# Tutorial.net
KiCad netlist of a schematic drawn in Altium Designer
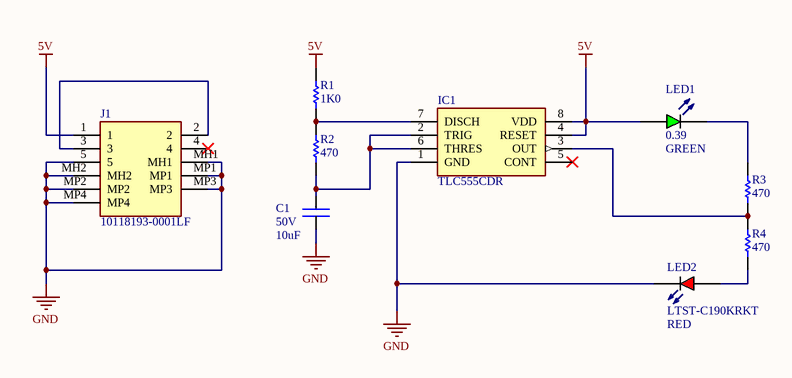
[diagram p0: Tutorial.SchDoc]

(export (version "E")
  (design (tool "Eeschema 10.0.6"))
  (components
    (comp (ref "C1")
      (value "10uF")
      (footprint "AquaDrone:CAPC3225X28N")
      (description "CAP CER 10UF 50V X7S 1210")
      (fields
        (field (name "MFG") "Taiyo Yuden")
        (field (name "MFG_PART_NO") "UMK325C7106MM-T")
        (field (name "VOLTAGE") "50V")
      )
      (libsource (lib "AquaDrone") (part "CAP CER 10UF 50V X7S 1210"))
    )
    (comp (ref "IC1")
      (value "TLC555CDR")
      (footprint "AquaDrone:SOIC127P600X175-8N")
      (description "Integrated Circuit")
      (fields (field (name "MOUSER PART NUMBER") "595-TLC555CDR") (field (name "RS PART NUMBER") "6624006P"))
      (libsource (lib "AquaDrone") (part "TLC555CDR"))
    )
    (comp (ref "J1")
      (value "10118193-0001LF")
      (footprint "AquaDrone:101181930001LF")
      (description "Connector")
      (fields
        (field (name "MOUSER PART NUMBER") "649-10118193-0001LF")
        (field (name "RS PART NUMBER") "8632989")
      )
      (libsource (lib "AquaDrone") (part "10118193-0001LF"))
    )
    (comp (ref "LED1")
      (value "GREEN")
      (footprint "AquaDrone:LED LTST-C190KGKT")
      (description "LED SUPER GREEN CLEAR 0603 SMD")
      (fields
        (field (name "MFG") "Lite-On")
        (field (name "MFG_PART_NO") "0.39")
        (field (name "Comment") "LED GREEN")
      )
      (libsource (lib "AquaDrone") (part "LED GREEN"))
    )
    (comp (ref "LED2")
      (value "RED")
      (footprint "AquaDrone:LED LTST-C190KRKT")
      (description "LED SUPER RED CLEAR 0603 SMD")
      (fields
        (field (name "MFG") "Lite-On")
        (field (name "MFG_PART_NO") "LTST-C190KRKT")
        (field (name "Comment") "LED RED")
      )
      (libsource (lib "AquaDrone") (part "LED RED"))
    )
    (comp (ref "R1")
      (value "1K0")
      (footprint "AquaDrone:RESC1608X06N")
      (description "RES SMD 1K OHM 1% 1/10W 0603")
      (fields (field (name "MFG") "Stackpole") (field (name "MFG_PART_NO") "RMCF0603FT1K00"))
      (libsource (lib "AquaDrone") (part "RES SMD 1K OHM 1% 1/10W 0603"))
    )
    (comp (ref "R2")
      (value "470")
      (footprint "AquaDrone:RESC1608X06N")
      (description "RES SMD 470 OHM 1% 1/10W 0603")
      (fields
        (field (name "MFG") "TE Connectivity Passive Product")
        (field (name "MFG_PART_NO") "CRGCQ0603J470R")
      )
      (libsource (lib "AquaDrone") (part "RES SMD 470 OHM 1% 1/10W 0603"))
    )
    (comp (ref "R3")
      (value "470")
      (footprint "AquaDrone:RESC1608X06N")
      (description "RES SMD 470 OHM 1% 1/10W 0603")
      (fields
        (field (name "MFG") "TE Connectivity Passive Product")
        (field (name "MFG_PART_NO") "CRGCQ0603J470R")
      )
      (libsource (lib "AquaDrone") (part "RES SMD 470 OHM 1% 1/10W 0603"))
    )
    (comp (ref "R4")
      (value "470")
      (footprint "AquaDrone:RESC1608X06N")
      (description "RES SMD 470 OHM 1% 1/10W 0603")
      (fields
        (field (name "MFG") "TE Connectivity Passive Product")
        (field (name "MFG_PART_NO") "CRGCQ0603J470R")
      )
      (libsource (lib "AquaDrone") (part "RES SMD 470 OHM 1% 1/10W 0603"))
    )
  )
  (nets
    (net (code "1") (name "5V") (class "Default")
      (node (ref "IC1") (pin "4") (pinfunction "RESET_4") (pintype "passive"))
      (node (ref "IC1") (pin "8") (pinfunction "VDD_8") (pintype "power_in"))
      (node (ref "J1") (pin "1") (pinfunction "1_1") (pintype "passive"))
      (node (ref "LED1") (pin "A") (pinfunction "A_A") (pintype "passive"))
      (node (ref "R1") (pin "2") (pinfunction "2_2") (pintype "passive"))
    )
    (net (code "2") (name "GND") (class "Default")
      (node (ref "C1") (pin "2") (pinfunction "2_2") (pintype "passive"))
      (node (ref "IC1") (pin "1") (pinfunction "GND_1") (pintype "power_in"))
      (node (ref "J1") (pin "5") (pinfunction "5_5") (pintype "passive"))
      (node (ref "J1") (pin "MH1") (pinfunction "MH1_MH1") (pintype "passive"))
      (node (ref "J1") (pin "MH2") (pinfunction "MH2_MH2") (pintype "passive"))
      (node (ref "J1") (pin "MP1") (pinfunction "MP1_MP1") (pintype "passive"))
      (node (ref "J1") (pin "MP2") (pinfunction "MP2_MP2") (pintype "passive"))
      (node (ref "J1") (pin "MP3") (pinfunction "MP3_MP3") (pintype "passive"))
      (node (ref "J1") (pin "MP4") (pinfunction "MP4_MP4") (pintype "passive"))
      (node (ref "LED2") (pin "K") (pinfunction "K_K") (pintype "passive"))
    )
    (net (code "3") (name "Net-(IC1-DISCH)") (class "Default")
      (node (ref "IC1") (pin "7") (pinfunction "DISCH_7") (pintype "passive"))
      (node (ref "R1") (pin "1") (pinfunction "1_1") (pintype "passive"))
      (node (ref "R2") (pin "1") (pinfunction "1_1") (pintype "passive"))
    )
    (net (code "4") (name "Net-(IC1-OUT)") (class "Default")
      (node (ref "IC1") (pin "3") (pinfunction "OUT_3") (pintype "output"))
      (node (ref "R3") (pin "1") (pinfunction "1_1") (pintype "passive"))
      (node (ref "R4") (pin "2") (pinfunction "2_2") (pintype "passive"))
    )
    (net (code "5") (name "Net-(IC1-THRES)") (class "Default")
      (node (ref "C1") (pin "1") (pinfunction "1_1") (pintype "passive"))
      (node (ref "IC1") (pin "2") (pinfunction "TRIG_2") (pintype "passive"))
      (node (ref "IC1") (pin "6") (pinfunction "THRES_6") (pintype "passive"))
      (node (ref "R2") (pin "2") (pinfunction "2_2") (pintype "passive"))
    )
    (net (code "6") (name "Net-(J1-Pad2)") (class "Default")
      (node (ref "J1") (pin "2") (pinfunction "2_2") (pintype "passive"))
      (node (ref "J1") (pin "3") (pinfunction "3_3") (pintype "passive"))
    )
    (net (code "7") (name "Net-(LED1-PadK)") (class "Default")
      (node (ref "LED1") (pin "K") (pinfunction "K_K") (pintype "passive"))
      (node (ref "R3") (pin "2") (pinfunction "2_2") (pintype "passive"))
    )
    (net (code "8") (name "Net-(LED2-PadA)") (class "Default")
      (node (ref "LED2") (pin "A") (pinfunction "A_A") (pintype "passive"))
      (node (ref "R4") (pin "1") (pinfunction "1_1") (pintype "passive"))
    )
    (net (code "9") (name "unconnected-(IC1-CONT-Pad5)") (class "Default")
      (node (ref "IC1") (pin "5") (pinfunction "CONT_5") (pintype "passive+no_connect"))
    )
    (net (code "10") (name "unconnected-(J1-Pad4)") (class "Default")
      (node (ref "J1") (pin "4") (pinfunction "4_4") (pintype "passive+no_connect"))
    )
  )
)
